# PWM_soldeerbout.net
KiCad netlist of a schematic drawn in Altium Designer
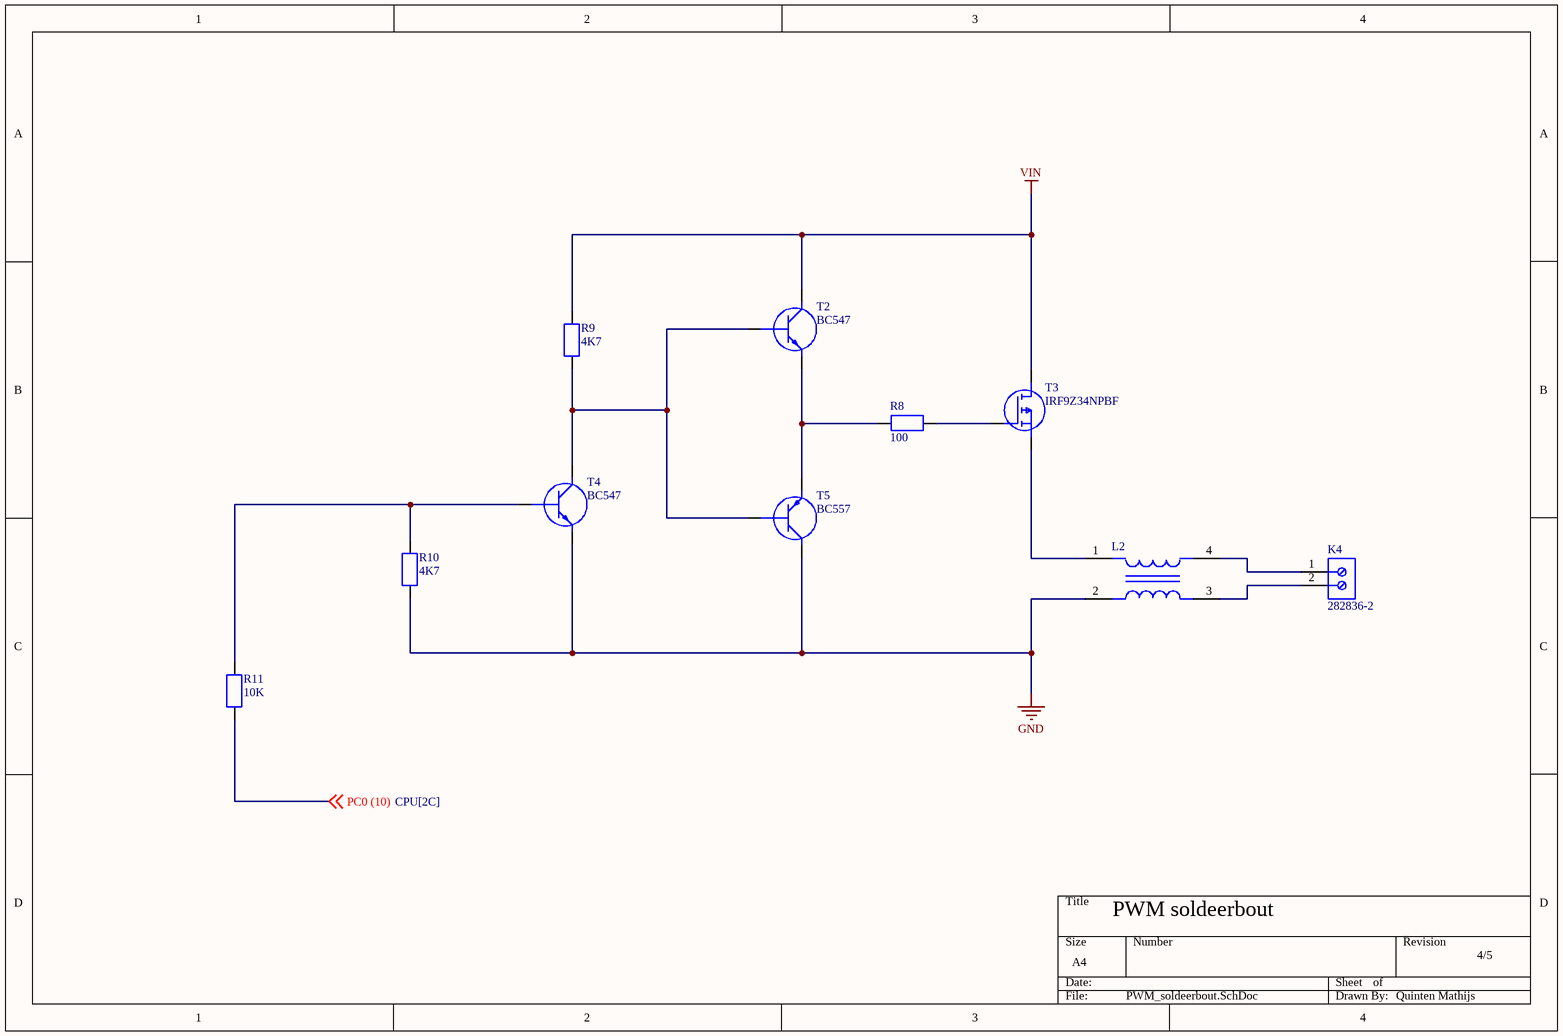
[diagram p0: PWM_soldeerbout.SchDoc]

(export (version "E")
  (design (tool "Eeschema 10.0.6"))
  (components
    (comp (ref "K4")
      (value "282836-2")
      (footprint "TECO-282836-2_V")
      (description "Female Header, Pitch 5 mm, 1 x 2 Position, Height 10 mm, Tail Length 3.5 mm, Rohs, Bulk")
      (fields (field (name "VOLTAGE") "300V") (field (name "MANUFACTURER") "TE Connectivity"))
      (libsource (lib "Schem_Soldeerstation") (part "CMP-1684-00017-1"))
    )
    (comp (ref "L2")
      (value "~")
      (footprint "2545")
      (libsource (lib "Schem_Soldeerstation") (part "Common_Mode_Choke"))
    )
    (comp (ref "R8")
      (value "100")
      (footprint "R_0805_L")
      (description "Resistor")
      (fields (field (name "MANUFACTURER") "Vishay Dale") (field (name "PART NUMBER") "CRCW08050000Z0EA"))
      (libsource (lib "Schem_Soldeerstation") (part "0805 (Resistor)"))
    )
    (comp (ref "R9")
      (value "4K7")
      (footprint "R_0805_L")
      (description "Resistor")
      (fields (field (name "MANUFACTURER") "Vishay Dale") (field (name "PART NUMBER") "CRCW08050000Z0EA"))
      (libsource (lib "Schem_Soldeerstation") (part "0805 (Resistor)"))
    )
    (comp (ref "R10")
      (value "4K7")
      (footprint "R_0805_L")
      (description "Resistor")
      (fields (field (name "MANUFACTURER") "Vishay Dale") (field (name "PART NUMBER") "CRCW08050000Z0EA"))
      (libsource (lib "Schem_Soldeerstation") (part "0805 (Resistor)"))
    )
    (comp (ref "R11")
      (value "10K")
      (footprint "R_0805_L")
      (description "Resistor")
      (fields (field (name "MANUFACTURER") "Vishay Dale") (field (name "PART NUMBER") "CRCW08050000Z0EA"))
      (libsource (lib "Schem_Soldeerstation") (part "0805 (Resistor)"))
    )
    (comp (ref "T2")
      (value "BC547")
      (footprint "SOT_23")
      (fields (field (name "MANUFACTURER") "On Semiconductor") (field (name "PARTNUMBER") "BC547C"))
      (libsource (lib "Schem_Soldeerstation") (part "Transistor_NPN"))
    )
    (comp (ref "T3")
      (value "IRF9Z34NPBF")
      (footprint "TO_252")
      (fields (field (name "MANUFACTURER") "Fairchild Semiconductor"))
      (libsource (lib "Schem_Soldeerstation") (part "MOSFET_P"))
    )
    (comp (ref "T4")
      (value "BC547")
      (footprint "SOT_23")
      (fields (field (name "MANUFACTURER") "On Semiconductor") (field (name "PARTNUMBER") "BC547C"))
      (libsource (lib "Schem_Soldeerstation") (part "Transistor_NPN"))
    )
    (comp (ref "T5")
      (value "BC557")
      (footprint "SOT_23")
      (fields (field (name "MANUFACTURER") "On Semiconductor") (field (name "PARTNUMBER") "BC557C"))
      (libsource (lib "Schem_Soldeerstation") (part "Transistor_PNP"))
    )
  )
  (nets
    (net (code "1") (name "GND") (class "Default")
      (node (ref "L2") (pin "2") (pinfunction "2_2") (pintype "passive"))
      (node (ref "R10") (pin "1") (pinfunction "1_1") (pintype "passive"))
      (node (ref "T4") (pin "3") (pinfunction "E_3") (pintype "passive"))
      (node (ref "T5") (pin "3") (pinfunction "C_3") (pintype "passive"))
    )
    (net (code "2") (name "Net-(K4-Pad1)") (class "Default")
      (node (ref "K4") (pin "1") (pinfunction "1_1") (pintype "passive"))
      (node (ref "L2") (pin "4") (pinfunction "4_4") (pintype "passive"))
    )
    (net (code "3") (name "Net-(K4-Pad2)") (class "Default")
      (node (ref "K4") (pin "2") (pinfunction "2_2") (pintype "passive"))
      (node (ref "L2") (pin "3") (pinfunction "3_3") (pintype "passive"))
    )
    (net (code "4") (name "Net-(T2-B)") (class "Default")
      (node (ref "R9") (pin "1") (pinfunction "1_1") (pintype "passive"))
      (node (ref "T2") (pin "2") (pinfunction "B_2") (pintype "passive"))
      (node (ref "T4") (pin "1") (pinfunction "C_1") (pintype "passive"))
      (node (ref "T5") (pin "2") (pinfunction "B_2") (pintype "passive"))
    )
    (net (code "5") (name "Net-(T2-E)") (class "Default")
      (node (ref "R8") (pin "1") (pinfunction "1_1") (pintype "passive"))
      (node (ref "T2") (pin "3") (pinfunction "E_3") (pintype "passive"))
      (node (ref "T5") (pin "1") (pinfunction "E_1") (pintype "passive"))
    )
    (net (code "6") (name "Net-(T3-G)") (class "Default")
      (node (ref "R8") (pin "2") (pinfunction "2_2") (pintype "passive"))
      (node (ref "T3") (pin "1") (pinfunction "G_1") (pintype "passive"))
    )
    (net (code "7") (name "Net-(T3-S)") (class "Default")
      (node (ref "L2") (pin "1") (pinfunction "1_1") (pintype "passive"))
      (node (ref "T3") (pin "2") (pinfunction "S_2") (pintype "passive"))
    )
    (net (code "8") (name "Net-(T4-B)") (class "Default")
      (node (ref "R10") (pin "2") (pinfunction "2_2") (pintype "passive"))
      (node (ref "R11") (pin "2") (pinfunction "2_2") (pintype "passive"))
      (node (ref "T4") (pin "2") (pinfunction "B_2") (pintype "passive"))
    )
    (net (code "9") (name "PC0 (10)") (class "Default")
      (node (ref "R11") (pin "1") (pinfunction "1_1") (pintype "passive"))
    )
    (net (code "10") (name "VIN") (class "Default")
      (node (ref "R9") (pin "2") (pinfunction "2_2") (pintype "passive"))
      (node (ref "T2") (pin "1") (pinfunction "C_1") (pintype "passive"))
      (node (ref "T3") (pin "3") (pinfunction "D_3") (pintype "passive"))
    )
  )
)
